# fsr_endstop_small.net
KiCad netlist of a schematic drawn in EAGLE
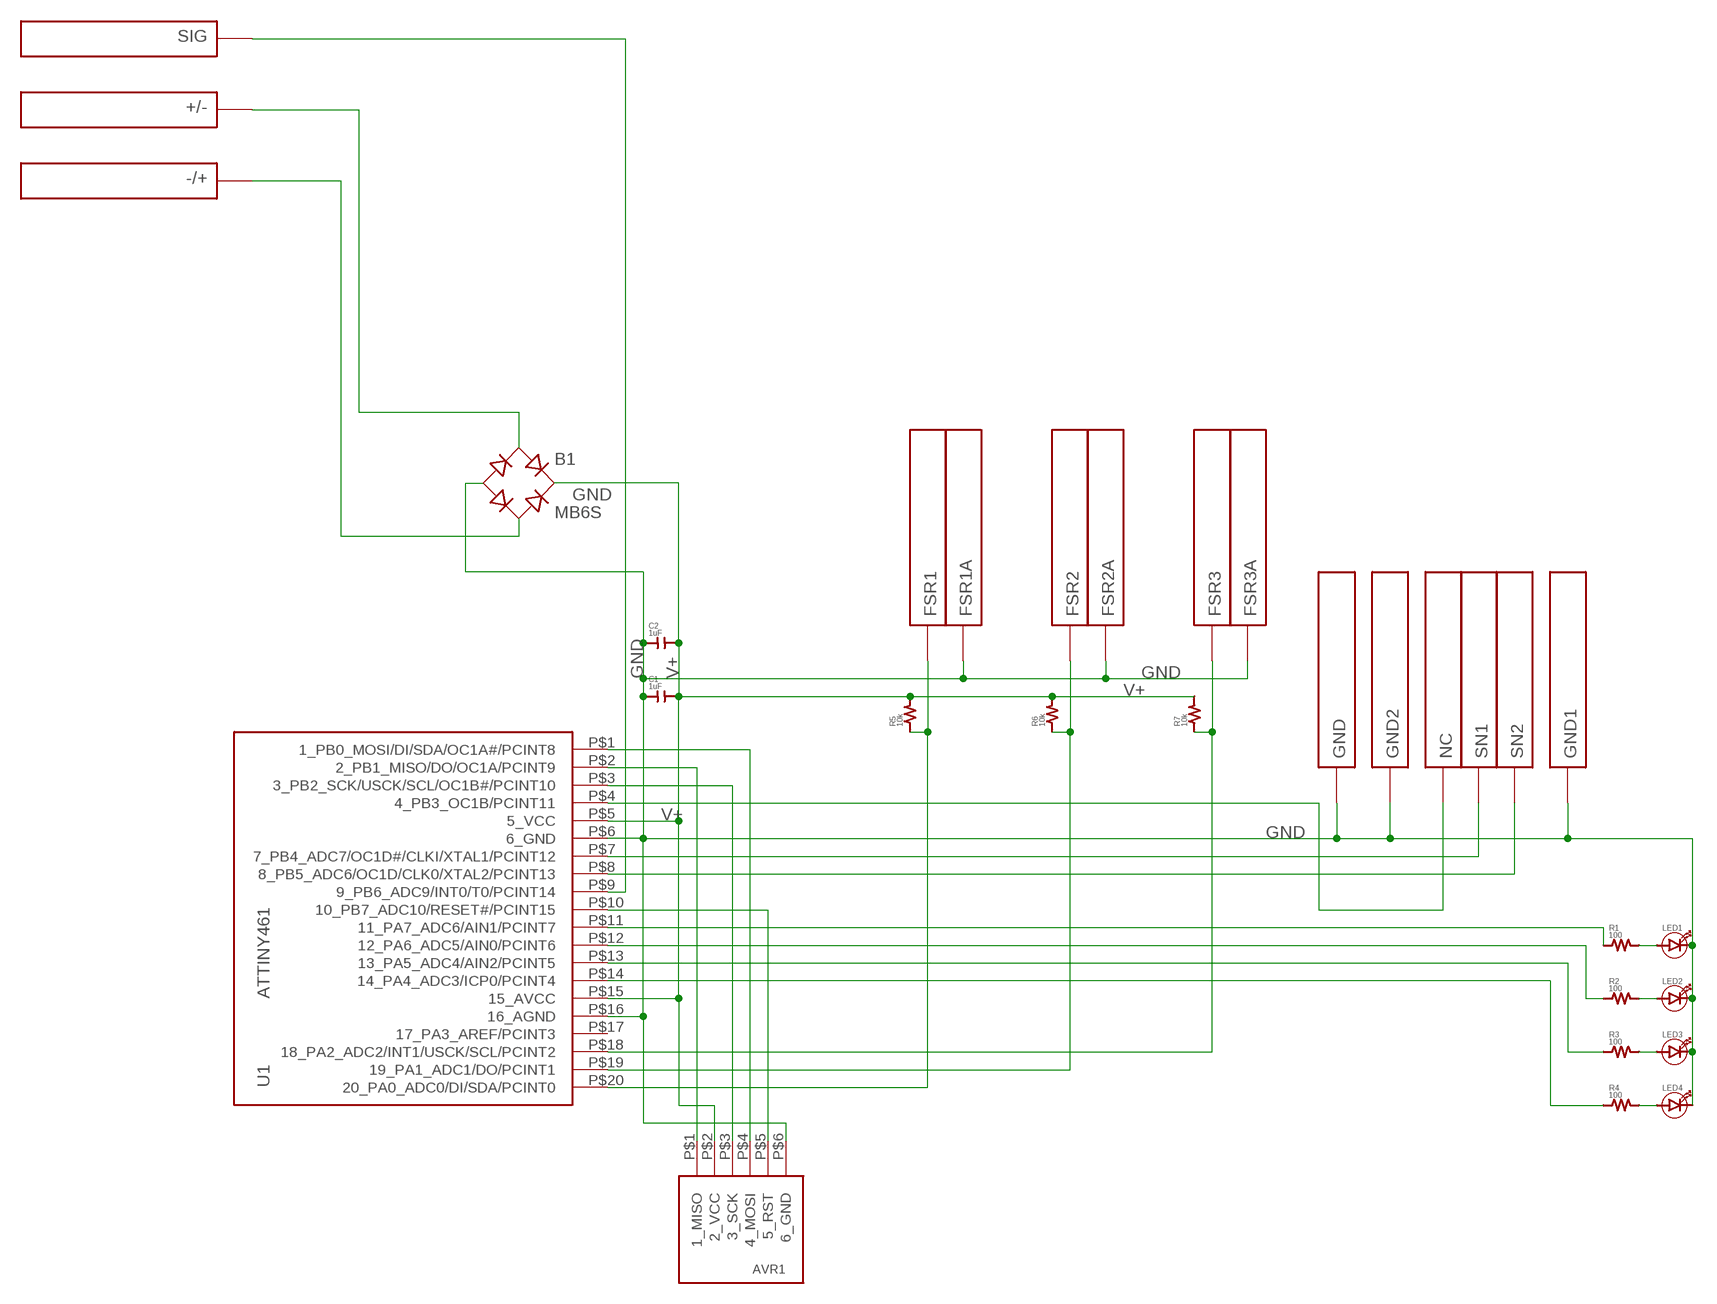
[diagram p0: schematic, sheet 1]

(export (version "E")
  (design (tool "Eeschema 10.0.6"))
  (components
    (comp (ref "+/-")
      (value "PIN1.2MM")
      (footprint "eagle-import:PIN_1.2MM")
      (libsource (lib "eagle-import") (part "PIN1.2MM"))
    )
    (comp (ref "-/+")
      (value "PIN1.2MM")
      (footprint "eagle-import:PIN_1.2MM")
      (libsource (lib "eagle-import") (part "PIN1.2MM"))
    )
    (comp (ref "AVR1")
      (value "AVR6")
      (footprint "eagle-import:AVR6")
      (libsource (lib "eagle-import") (part "AVR6"))
    )
    (comp (ref "B1")
      (value "MB6S")
      (footprint "eagle-import:SOIC-4")
      (libsource (lib "eagle-import") (part "MBS6"))
    )
    (comp (ref "C1")
      (value "1uF")
      (footprint "eagle-import:0603")
      (libsource (lib "eagle-import") (part "CAP0603"))
    )
    (comp (ref "C2")
      (value "1uF")
      (footprint "eagle-import:0603")
      (libsource (lib "eagle-import") (part "CAP0603"))
    )
    (comp (ref "FSR1")
      (value "PIN1.2MM")
      (footprint "eagle-import:PIN_1.2MM")
      (libsource (lib "eagle-import") (part "PIN1.2MM"))
    )
    (comp (ref "FSR1A")
      (value "PIN1.2MM")
      (footprint "eagle-import:PIN_1.2MM")
      (libsource (lib "eagle-import") (part "PIN1.2MM"))
    )
    (comp (ref "FSR2")
      (value "PIN1.2MM")
      (footprint "eagle-import:PIN_1.2MM")
      (libsource (lib "eagle-import") (part "PIN1.2MM"))
    )
    (comp (ref "FSR2A")
      (value "PIN1.2MM")
      (footprint "eagle-import:PIN_1.2MM")
      (libsource (lib "eagle-import") (part "PIN1.2MM"))
    )
    (comp (ref "FSR3")
      (value "PIN1.2MM")
      (footprint "eagle-import:PIN_1.2MM")
      (libsource (lib "eagle-import") (part "PIN1.2MM"))
    )
    (comp (ref "FSR3A")
      (value "PIN1.2MM")
      (footprint "eagle-import:PIN_1.2MM")
      (libsource (lib "eagle-import") (part "PIN1.2MM"))
    )
    (comp (ref "GND")
      (value "PIN1.2MM")
      (footprint "eagle-import:PIN_1.2MM")
      (libsource (lib "eagle-import") (part "PIN1.2MM"))
    )
    (comp (ref "GND1")
      (value "PIN1.2MM")
      (footprint "eagle-import:PIN_1.2MM")
      (libsource (lib "eagle-import") (part "PIN1.2MM"))
    )
    (comp (ref "GND2")
      (value "PIN1.2MM")
      (footprint "eagle-import:PIN_1.2MM")
      (libsource (lib "eagle-import") (part "PIN1.2MM"))
    )
    (comp (ref "LED1")
      (value "LED0603")
      (footprint "eagle-import:0603_DIODE")
      (libsource (lib "eagle-import") (part "LED0603"))
    )
    (comp (ref "LED2")
      (value "LED0603")
      (footprint "eagle-import:0603_DIODE")
      (libsource (lib "eagle-import") (part "LED0603"))
    )
    (comp (ref "LED3")
      (value "LED0603")
      (footprint "eagle-import:0603_DIODE")
      (libsource (lib "eagle-import") (part "LED0603"))
    )
    (comp (ref "LED4")
      (value "LED0603")
      (footprint "eagle-import:0603_DIODE")
      (libsource (lib "eagle-import") (part "LED0603"))
    )
    (comp (ref "NC")
      (value "PIN1.2MM")
      (footprint "eagle-import:PIN_1.2MM")
      (libsource (lib "eagle-import") (part "PIN1.2MM"))
    )
    (comp (ref "R1")
      (value "100")
      (footprint "eagle-import:0603")
      (libsource (lib "eagle-import") (part "RES0603"))
    )
    (comp (ref "R2")
      (value "100")
      (footprint "eagle-import:0603")
      (libsource (lib "eagle-import") (part "RES0603"))
    )
    (comp (ref "R3")
      (value "100")
      (footprint "eagle-import:0603")
      (libsource (lib "eagle-import") (part "RES0603"))
    )
    (comp (ref "R4")
      (value "100")
      (footprint "eagle-import:0603")
      (libsource (lib "eagle-import") (part "RES0603"))
    )
    (comp (ref "R5")
      (value "10k")
      (footprint "eagle-import:0603")
      (libsource (lib "eagle-import") (part "RES0603"))
    )
    (comp (ref "R6")
      (value "10k")
      (footprint "eagle-import:0603")
      (libsource (lib "eagle-import") (part "RES0603"))
    )
    (comp (ref "R7")
      (value "10k")
      (footprint "eagle-import:0603")
      (libsource (lib "eagle-import") (part "RES0603"))
    )
    (comp (ref "SIG")
      (value "PIN1.2MM")
      (footprint "eagle-import:PIN_1.2MM")
      (libsource (lib "eagle-import") (part "PIN1.2MM"))
    )
    (comp (ref "SN1")
      (value "PIN1.2MM")
      (footprint "eagle-import:PIN_1.2MM")
      (libsource (lib "eagle-import") (part "PIN1.2MM"))
    )
    (comp (ref "SN2")
      (value "PIN1.2MM")
      (footprint "eagle-import:PIN_1.2MM")
      (libsource (lib "eagle-import") (part "PIN1.2MM"))
    )
    (comp (ref "U1")
      (value "ATTINY461")
      (footprint "eagle-import:SOIC-20")
      (libsource (lib "eagle-import") (part "ATTINY461"))
    )
  )
  (nets
    (net (code "1") (name "/GND") (class "Default")
      (node (ref "AVR1") (pin "P$6") (pinfunction "6_GND_P$6") (pintype "bidirectional"))
      (node (ref "B1") (pin "-") (pinfunction "-_-") (pintype "passive"))
      (node (ref "C1") (pin "1") (pinfunction "P$1_1") (pintype "bidirectional"))
      (node (ref "C2") (pin "1") (pinfunction "P$1_1") (pintype "bidirectional"))
      (node (ref "FSR1A") (pin "P$1") (pinfunction "P$1_P$1") (pintype "bidirectional"))
      (node (ref "FSR2A") (pin "P$1") (pinfunction "P$1_P$1") (pintype "bidirectional"))
      (node (ref "FSR3A") (pin "P$1") (pinfunction "P$1_P$1") (pintype "bidirectional"))
      (node (ref "GND") (pin "P$1") (pinfunction "P$1_P$1") (pintype "bidirectional"))
      (node (ref "GND1") (pin "P$1") (pinfunction "P$1_P$1") (pintype "bidirectional"))
      (node (ref "GND2") (pin "P$1") (pinfunction "P$1_P$1") (pintype "bidirectional"))
      (node (ref "LED1") (pin "-") (pinfunction "-_-") (pintype "bidirectional"))
      (node (ref "LED2") (pin "-") (pinfunction "-_-") (pintype "bidirectional"))
      (node (ref "LED3") (pin "-") (pinfunction "-_-") (pintype "bidirectional"))
      (node (ref "LED4") (pin "-") (pinfunction "-_-") (pintype "bidirectional"))
      (node (ref "U1") (pin "P$16") (pinfunction "16_AGND_P$16") (pintype "bidirectional"))
      (node (ref "U1") (pin "P$6") (pinfunction "6_GND_P$6") (pintype "bidirectional"))
    )
    (net (code "2") (name "/V+") (class "Default")
      (node (ref "AVR1") (pin "P$2") (pinfunction "2_VCC_P$2") (pintype "bidirectional"))
      (node (ref "B1") (pin "+") (pinfunction "+_+") (pintype "passive"))
      (node (ref "C1") (pin "2") (pinfunction "P$2_2") (pintype "bidirectional"))
      (node (ref "C2") (pin "2") (pinfunction "P$2_2") (pintype "bidirectional"))
      (node (ref "R5") (pin "2") (pinfunction "P$2_2") (pintype "bidirectional"))
      (node (ref "R6") (pin "2") (pinfunction "P$2_2") (pintype "bidirectional"))
      (node (ref "R7") (pin "2") (pinfunction "P$2_2") (pintype "bidirectional"))
      (node (ref "U1") (pin "P$15") (pinfunction "15_AVCC_P$15") (pintype "bidirectional"))
      (node (ref "U1") (pin "P$5") (pinfunction "5_VCC_P$5") (pintype "bidirectional"))
    )
    (net (code "3") (name "Net-(AVR1-1_MISO)") (class "Default")
      (node (ref "AVR1") (pin "P$1") (pinfunction "1_MISO_P$1") (pintype "bidirectional"))
      (node (ref "U1") (pin "P$2") (pinfunction "2_PB1_MISO/DO/OC1A/PCINT9_P$2") (pintype "bidirectional"))
    )
    (net (code "4") (name "Net-(AVR1-3_SCK)") (class "Default")
      (node (ref "AVR1") (pin "P$3") (pinfunction "3_SCK_P$3") (pintype "bidirectional"))
      (node (ref "U1") (pin "P$3") (pinfunction "3_PB2_SCK/USCK/SCL/OC1B#/PCINT10_P$3") (pintype "bidirectional"))
    )
    (net (code "5") (name "Net-(AVR1-4_MOSI)") (class "Default")
      (node (ref "AVR1") (pin "P$4") (pinfunction "4_MOSI_P$4") (pintype "bidirectional"))
      (node (ref "U1") (pin "P$1") (pinfunction "1_PB0_MOSI/DI/SDA/OC1A#/PCINT8_P$1") (pintype "bidirectional"))
    )
    (net (code "6") (name "Net-(AVR1-5_RST)") (class "Default")
      (node (ref "AVR1") (pin "P$5") (pinfunction "5_RST_P$5") (pintype "bidirectional"))
      (node (ref "U1") (pin "P$10") (pinfunction "10_PB7_ADC10/RESET#/PCINT15_P$10") (pintype "bidirectional"))
    )
    (net (code "7") (name "Net-(B1-AC1)") (class "Default")
      (node (ref "+/-") (pin "P$1") (pinfunction "P$1_P$1") (pintype "bidirectional"))
      (node (ref "B1") (pin "~1") (pinfunction "AC1_~1") (pintype "passive"))
    )
    (net (code "8") (name "Net-(B1-AC2)") (class "Default")
      (node (ref "-/+") (pin "P$1") (pinfunction "P$1_P$1") (pintype "bidirectional"))
      (node (ref "B1") (pin "~2") (pinfunction "AC2_~2") (pintype "passive"))
    )
    (net (code "9") (name "Net-(R1-P$1)") (class "Default")
      (node (ref "R1") (pin "1") (pinfunction "P$1_1") (pintype "bidirectional"))
      (node (ref "U1") (pin "P$11") (pinfunction "11_PA7_ADC6/AIN1/PCINT7_P$11") (pintype "bidirectional"))
    )
    (net (code "10") (name "Net-(R1-P$2)") (class "Default")
      (node (ref "LED1") (pin "+") (pinfunction "+_+") (pintype "bidirectional"))
      (node (ref "R1") (pin "2") (pinfunction "P$2_2") (pintype "bidirectional"))
    )
    (net (code "11") (name "Net-(R2-P$1)") (class "Default")
      (node (ref "R2") (pin "1") (pinfunction "P$1_1") (pintype "bidirectional"))
      (node (ref "U1") (pin "P$12") (pinfunction "12_PA6_ADC5/AIN0/PCINT6_P$12") (pintype "bidirectional"))
    )
    (net (code "12") (name "Net-(R2-P$2)") (class "Default")
      (node (ref "LED2") (pin "+") (pinfunction "+_+") (pintype "bidirectional"))
      (node (ref "R2") (pin "2") (pinfunction "P$2_2") (pintype "bidirectional"))
    )
    (net (code "13") (name "Net-(R3-P$1)") (class "Default")
      (node (ref "R3") (pin "1") (pinfunction "P$1_1") (pintype "bidirectional"))
      (node (ref "U1") (pin "P$13") (pinfunction "13_PA5_ADC4/AIN2/PCINT5_P$13") (pintype "bidirectional"))
    )
    (net (code "14") (name "Net-(R3-P$2)") (class "Default")
      (node (ref "LED3") (pin "+") (pinfunction "+_+") (pintype "bidirectional"))
      (node (ref "R3") (pin "2") (pinfunction "P$2_2") (pintype "bidirectional"))
    )
    (net (code "15") (name "Net-(R4-P$1)") (class "Default")
      (node (ref "R4") (pin "1") (pinfunction "P$1_1") (pintype "bidirectional"))
      (node (ref "U1") (pin "P$14") (pinfunction "14_PA4_ADC3/ICP0/PCINT4_P$14") (pintype "bidirectional"))
    )
    (net (code "16") (name "Net-(R4-P$2)") (class "Default")
      (node (ref "LED4") (pin "+") (pinfunction "+_+") (pintype "bidirectional"))
      (node (ref "R4") (pin "2") (pinfunction "P$2_2") (pintype "bidirectional"))
    )
    (net (code "17") (name "Net-(R5-P$1)") (class "Default")
      (node (ref "FSR1") (pin "P$1") (pinfunction "P$1_P$1") (pintype "bidirectional"))
      (node (ref "R5") (pin "1") (pinfunction "P$1_1") (pintype "bidirectional"))
      (node (ref "U1") (pin "P$20") (pinfunction "20_PA0_ADC0/DI/SDA/PCINT0_P$20") (pintype "bidirectional"))
    )
    (net (code "18") (name "Net-(R6-P$1)") (class "Default")
      (node (ref "FSR2") (pin "P$1") (pinfunction "P$1_P$1") (pintype "bidirectional"))
      (node (ref "R6") (pin "1") (pinfunction "P$1_1") (pintype "bidirectional"))
      (node (ref "U1") (pin "P$19") (pinfunction "19_PA1_ADC1/DO/PCINT1_P$19") (pintype "bidirectional"))
    )
    (net (code "19") (name "Net-(R7-P$1)") (class "Default")
      (node (ref "FSR3") (pin "P$1") (pinfunction "P$1_P$1") (pintype "bidirectional"))
      (node (ref "R7") (pin "1") (pinfunction "P$1_1") (pintype "bidirectional"))
      (node (ref "U1") (pin "P$18") (pinfunction "18_PA2_ADC2/INT1/USCK/SCL/PCINT2_P$18") (pintype "bidirectional"))
    )
    (net (code "20") (name "Net-(U1-4_PB3_OC1B{slash}PCINT11)") (class "Default")
      (node (ref "NC") (pin "P$1") (pinfunction "P$1_P$1") (pintype "bidirectional"))
      (node (ref "U1") (pin "P$4") (pinfunction "4_PB3_OC1B/PCINT11_P$4") (pintype "bidirectional"))
    )
    (net (code "21") (name "Net-(U1-7_PB4_ADC7{slash}OC1D#{slash}CLKI{slash}XTAL1{slash}PCINT12)") (class "Default")
      (node (ref "SN1") (pin "P$1") (pinfunction "P$1_P$1") (pintype "bidirectional"))
      (node (ref "U1") (pin "P$7") (pinfunction "7_PB4_ADC7/OC1D#/CLKI/XTAL1/PCINT12_P$7") (pintype "bidirectional"))
    )
    (net (code "22") (name "Net-(U1-8_PB5_ADC6{slash}OC1D{slash}CLK0{slash}XTAL2{slash}PCINT13)") (class "Default")
      (node (ref "SN2") (pin "P$1") (pinfunction "P$1_P$1") (pintype "bidirectional"))
      (node (ref "U1") (pin "P$8") (pinfunction "8_PB5_ADC6/OC1D/CLK0/XTAL2/PCINT13_P$8") (pintype "bidirectional"))
    )
    (net (code "23") (name "Net-(U1-9_PB6_ADC9{slash}INT0{slash}T0{slash}PCINT14)") (class "Default")
      (node (ref "SIG") (pin "P$1") (pinfunction "P$1_P$1") (pintype "bidirectional"))
      (node (ref "U1") (pin "P$9") (pinfunction "9_PB6_ADC9/INT0/T0/PCINT14_P$9") (pintype "bidirectional"))
    )
    (net (code "24") (name "unconnected-(U1-17_PA3_AREF{slash}PCINT3-PadP$17)") (class "Default")
      (node (ref "U1") (pin "P$17") (pinfunction "17_PA3_AREF/PCINT3_P$17") (pintype "bidirectional"))
    )
  )
)
